# FLEXQCM_V1_1.net
KiCad netlist of a schematic drawn in EAGLE
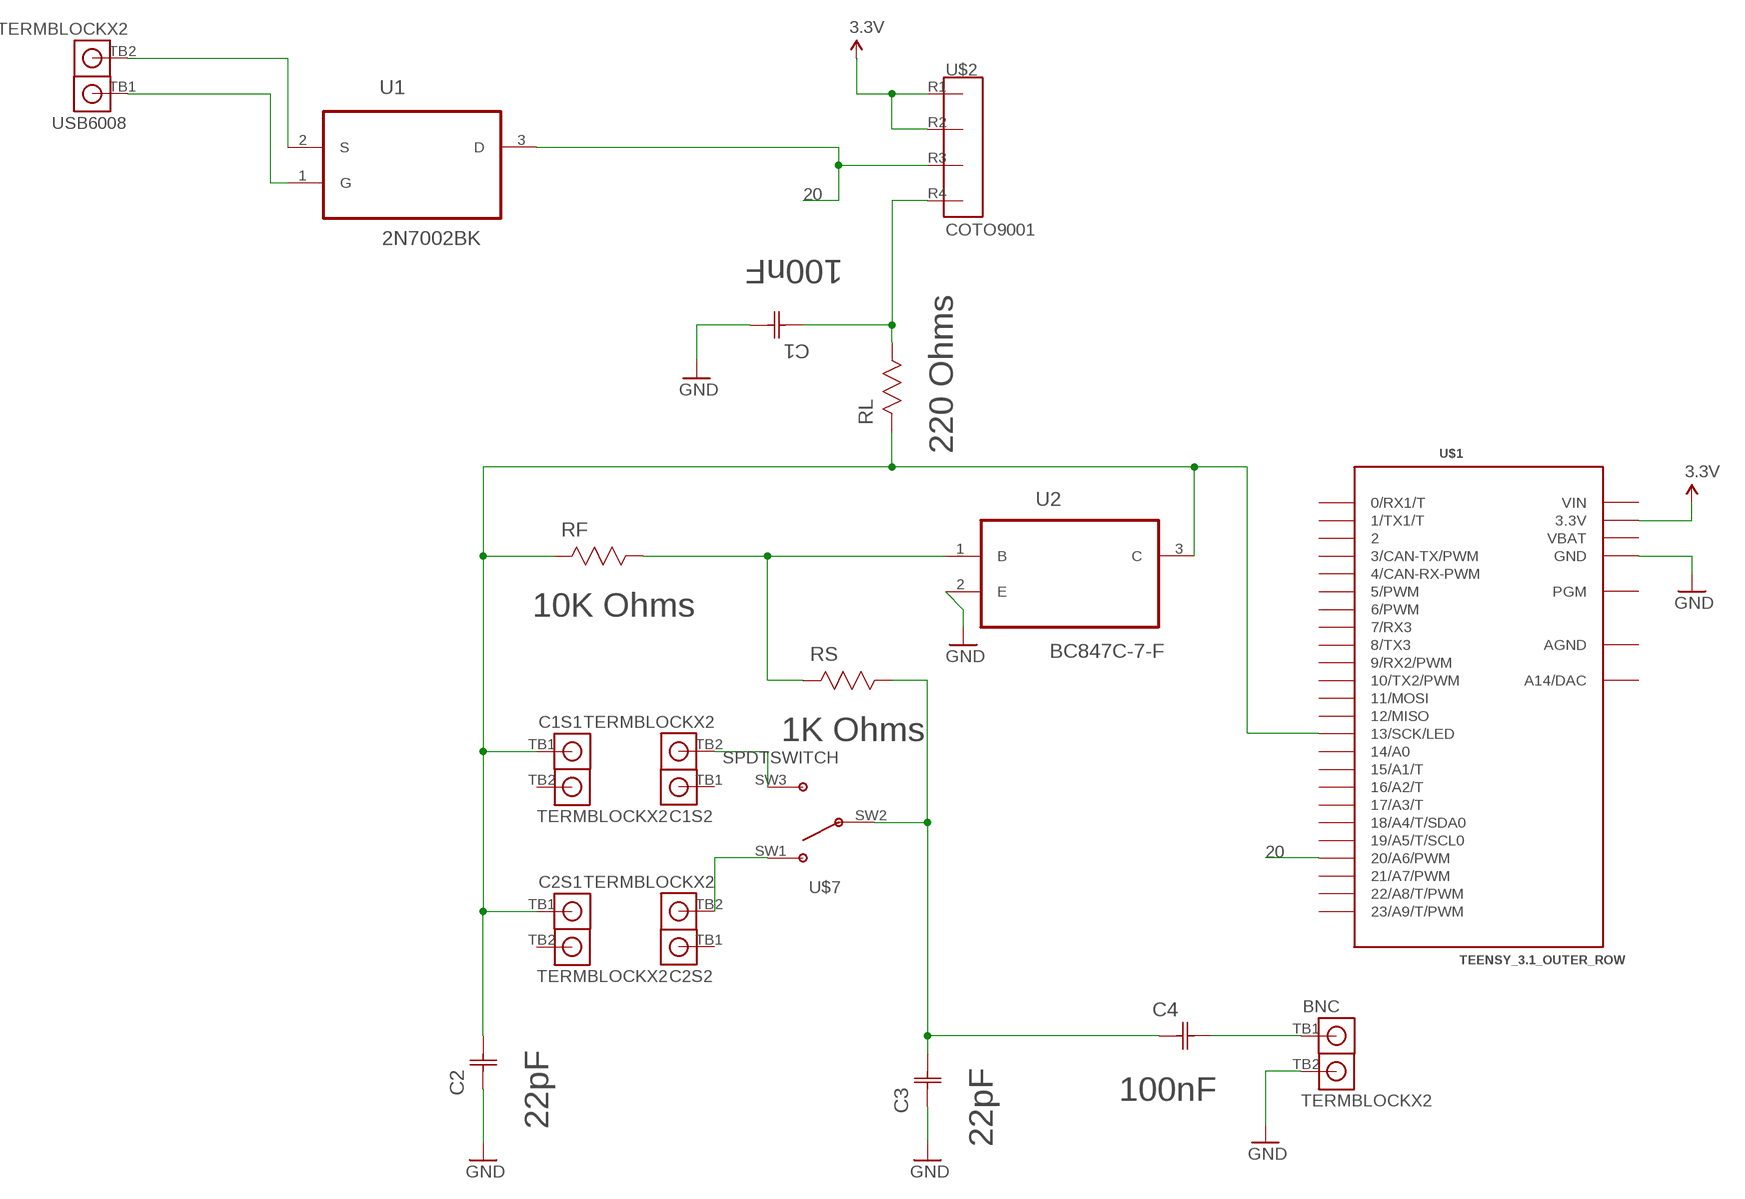
[diagram p0: schematic, sheet 1]

(export (version "E")
  (design (tool "Eeschema 10.0.6"))
  (components
    (comp (ref "BNC")
      (value "TERMBLOCKX2")
      (footprint "eagle-import:TERMBLOCKX2")
      (libsource (lib "eagle-import") (part "TERMBLOCKX2"))
    )
    (comp (ref "C1")
      (value "100nF")
      (footprint "eagle-import:CAPC3216X88N")
      (fields (field (name "MPN") "C1206C104K1RACTU") (field (name "TOLERANCE") "±10%"))
      (libsource (lib "eagle-import") (part "C1206C104K1RACTU"))
    )
    (comp (ref "C1S1")
      (value "TERMBLOCKX2")
      (footprint "eagle-import:TERMBLOCKX2")
      (libsource (lib "eagle-import") (part "TERMBLOCKX2"))
    )
    (comp (ref "C1S2")
      (value "TERMBLOCKX2")
      (footprint "eagle-import:TERMBLOCKX2")
      (libsource (lib "eagle-import") (part "TERMBLOCKX2"))
    )
    (comp (ref "C2")
      (value "22pF")
      (footprint "eagle-import:CAPC3216X88N")
      (fields (field (name "MPN") "C1206C220J5GACTU") (field (name "TOLERANCE") "±5%"))
      (libsource (lib "eagle-import") (part "C1206C220J5GACTU"))
    )
    (comp (ref "C2S1")
      (value "TERMBLOCKX2")
      (footprint "eagle-import:TERMBLOCKX2")
      (libsource (lib "eagle-import") (part "TERMBLOCKX2"))
    )
    (comp (ref "C2S2")
      (value "TERMBLOCKX2")
      (footprint "eagle-import:TERMBLOCKX2")
      (libsource (lib "eagle-import") (part "TERMBLOCKX2"))
    )
    (comp (ref "C3")
      (value "22pF")
      (footprint "eagle-import:CAPC3216X88N")
      (fields (field (name "MPN") "C1206C220J5GACTU") (field (name "TOLERANCE") "±5%"))
      (libsource (lib "eagle-import") (part "C1206C220J5GACTU"))
    )
    (comp (ref "C4")
      (value "100nF")
      (footprint "eagle-import:CAPC3216X88N")
      (fields (field (name "MPN") "C1206C104K1RACTU") (field (name "TOLERANCE") "±10%"))
      (libsource (lib "eagle-import") (part "C1206C104K1RACTU"))
    )
    (comp (ref "RF")
      (value "10K Ohms")
      (footprint "eagle-import:RESC3216X71N")
      (fields (field (name "MPN") "CRCW120610K0FKEA") (field (name "TOLERANCE") "±1%"))
      (libsource (lib "eagle-import") (part "CRCW120610K0FKEA"))
    )
    (comp (ref "RL")
      (value "220 Ohms")
      (footprint "eagle-import:RESC3216X71N")
      (fields (field (name "MPN") "CRCW1206220RJNEA") (field (name "TOLERANCE") "±5%"))
      (libsource (lib "eagle-import") (part "CRCW1206220RJNEA"))
    )
    (comp (ref "RS")
      (value "1K Ohms")
      (footprint "eagle-import:RESC3216X71N")
      (fields (field (name "MPN") "CRCW12061K00FKEA") (field (name "TOLERANCE") "±1%"))
      (libsource (lib "eagle-import") (part "CRCW12061K00FKEA"))
    )
    (comp (ref "U$1")
      (value "TEENSY_3.1_OUTER_ROW")
      (footprint "eagle-import:TEENSY3-OUTER_ROW")
      (libsource (lib "eagle-import") (part "TEENSY_3.1_OUTER_ROW"))
    )
    (comp (ref "U$2")
      (value "COTO9001")
      (footprint "eagle-import:COTO9001")
      (libsource (lib "eagle-import") (part "COTO9001"))
    )
    (comp (ref "U$7")
      (value "SPDTSWITCH")
      (footprint "eagle-import:SPDTSWITCH")
      (libsource (lib "eagle-import") (part "SPDTSWITCH"))
    )
    (comp (ref "U1")
      (value "2N7002BK")
      (footprint "eagle-import:SOT95P230X110-3N")
      (libsource (lib "eagle-import") (part "2N7002BK"))
    )
    (comp (ref "U2")
      (value "BC847C-7-F")
      (footprint "eagle-import:SOT103P240X110-3N")
      (libsource (lib "eagle-import") (part "BC847C-7-F"))
    )
    (comp (ref "USB6008")
      (value "TERMBLOCKX2")
      (footprint "eagle-import:TERMBLOCKX2")
      (libsource (lib "eagle-import") (part "TERMBLOCKX2"))
    )
  )
  (nets
    (net (code "1") (name "/20") (class "Default")
      (node (ref "U$1") (pin "20/A6") (pinfunction "20/A6/PWM_20/A6") (pintype "bidirectional"))
      (node (ref "U$2") (pin "R3") (pinfunction "R3_R3") (pintype "bidirectional"))
      (node (ref "U1") (pin "3") (pinfunction "D_3") (pintype "passive"))
    )
    (net (code "2") (name "/AGND") (class "Default")
      (node (ref "U$1") (pin "AGND") (pinfunction "AGND_AGND") (pintype "power_in"))
    )
    (net (code "3") (name "/VBAT") (class "Default")
      (node (ref "U$1") (pin "VBAT") (pinfunction "VBAT_VBAT") (pintype "power_in"))
    )
    (net (code "4") (name "/VIN") (class "Default")
      (node (ref "U$1") (pin "VIN") (pinfunction "VIN_VIN") (pintype "power_in"))
    )
    (net (code "5") (name "3.3V") (class "Default")
      (node (ref "U$1") (pin "3.3V") (pinfunction "3.3V_3.3V") (pintype "power_in"))
      (node (ref "U$1") (pin "3.3V1") (pinfunction "3.3V_3.3V1") (pintype "power_in"))
      (node (ref "U$2") (pin "R1") (pinfunction "R1_R1") (pintype "bidirectional"))
      (node (ref "U$2") (pin "R2") (pinfunction "R2_R2") (pintype "bidirectional"))
    )
    (net (code "6") (name "GND") (class "Default")
      (node (ref "BNC") (pin "TB2") (pinfunction "TB2_TB2") (pintype "bidirectional"))
      (node (ref "C1") (pin "2") (pinfunction "C2_2") (pintype "passive"))
      (node (ref "C2") (pin "1") (pinfunction "C1_1") (pintype "passive"))
      (node (ref "C3") (pin "1") (pinfunction "C1_1") (pintype "passive"))
      (node (ref "U$1") (pin "GND") (pinfunction "GND_GND") (pintype "power_in"))
      (node (ref "U$1") (pin "GND1") (pinfunction "GND_GND1") (pintype "power_in"))
      (node (ref "U2") (pin "2") (pinfunction "E_2") (pintype "passive"))
    )
    (net (code "7") (name "Net-(C1-C1)") (class "Default")
      (node (ref "C1") (pin "1") (pinfunction "C1_1") (pintype "passive"))
      (node (ref "RL") (pin "1") (pinfunction "1_1") (pintype "passive"))
      (node (ref "U$2") (pin "R4") (pinfunction "R4_R4") (pintype "bidirectional"))
    )
    (net (code "8") (name "Net-(C1S2-PadTB2)") (class "Default")
      (node (ref "C1S2") (pin "TB2") (pinfunction "TB2_TB2") (pintype "bidirectional"))
      (node (ref "U$7") (pin "SW3") (pinfunction "SW3_SW3") (pintype "bidirectional"))
    )
    (net (code "9") (name "Net-(C2-C2)") (class "Default")
      (node (ref "C1S1") (pin "TB1") (pinfunction "TB1_TB1") (pintype "bidirectional"))
      (node (ref "C2") (pin "2") (pinfunction "C2_2") (pintype "passive"))
      (node (ref "C2S1") (pin "TB1") (pinfunction "TB1_TB1") (pintype "bidirectional"))
      (node (ref "RF") (pin "2") (pinfunction "2_2") (pintype "passive"))
      (node (ref "RL") (pin "2") (pinfunction "2_2") (pintype "passive"))
      (node (ref "U$1") (pin "13") (pinfunction "13/SCK/LED_13") (pintype "bidirectional"))
      (node (ref "U2") (pin "3") (pinfunction "C_3") (pintype "output"))
    )
    (net (code "10") (name "Net-(C2S2-PadTB2)") (class "Default")
      (node (ref "C2S2") (pin "TB2") (pinfunction "TB2_TB2") (pintype "bidirectional"))
      (node (ref "U$7") (pin "SW1") (pinfunction "SW1_SW1") (pintype "bidirectional"))
    )
    (net (code "11") (name "Net-(C3-C2)") (class "Default")
      (node (ref "C3") (pin "2") (pinfunction "C2_2") (pintype "passive"))
      (node (ref "C4") (pin "1") (pinfunction "C1_1") (pintype "passive"))
      (node (ref "RS") (pin "1") (pinfunction "1_1") (pintype "passive"))
      (node (ref "U$7") (pin "SW2") (pinfunction "SW2_SW2") (pintype "bidirectional"))
    )
    (net (code "12") (name "Net-(C4-C2)") (class "Default")
      (node (ref "BNC") (pin "TB1") (pinfunction "TB1_TB1") (pintype "bidirectional"))
      (node (ref "C4") (pin "2") (pinfunction "C2_2") (pintype "passive"))
    )
    (net (code "13") (name "Net-(U1-G)") (class "Default")
      (node (ref "U1") (pin "1") (pinfunction "G_1") (pintype "passive"))
      (node (ref "USB6008") (pin "TB1") (pinfunction "TB1_TB1") (pintype "bidirectional"))
    )
    (net (code "14") (name "Net-(U1-S)") (class "Default")
      (node (ref "U1") (pin "2") (pinfunction "S_2") (pintype "passive"))
      (node (ref "USB6008") (pin "TB2") (pinfunction "TB2_TB2") (pintype "bidirectional"))
    )
    (net (code "15") (name "Net-(U2-B)") (class "Default")
      (node (ref "RF") (pin "1") (pinfunction "1_1") (pintype "passive"))
      (node (ref "RS") (pin "2") (pinfunction "2_2") (pintype "passive"))
      (node (ref "U2") (pin "1") (pinfunction "B_1") (pintype "input"))
    )
    (net (code "16") (name "unconnected-(C1S1-PadTB2)") (class "Default")
      (node (ref "C1S1") (pin "TB2") (pinfunction "TB2_TB2") (pintype "bidirectional"))
    )
    (net (code "17") (name "unconnected-(C1S2-PadTB1)") (class "Default")
      (node (ref "C1S2") (pin "TB1") (pinfunction "TB1_TB1") (pintype "bidirectional"))
    )
    (net (code "18") (name "unconnected-(C2S1-PadTB2)") (class "Default")
      (node (ref "C2S1") (pin "TB2") (pinfunction "TB2_TB2") (pintype "bidirectional"))
    )
    (net (code "19") (name "unconnected-(C2S2-PadTB1)") (class "Default")
      (node (ref "C2S2") (pin "TB1") (pinfunction "TB1_TB1") (pintype "bidirectional"))
    )
    (net (code "20") (name "unconnected-(U$1-0{slash}RX1{slash}T-Pad0)") (class "Default")
      (node (ref "U$1") (pin "0") (pinfunction "0/RX1/T_0") (pintype "bidirectional"))
    )
    (net (code "21") (name "unconnected-(U$1-1{slash}TX1{slash}T-Pad1)") (class "Default")
      (node (ref "U$1") (pin "1") (pinfunction "1/TX1/T_1") (pintype "bidirectional"))
    )
    (net (code "22") (name "unconnected-(U$1-3{slash}CAN-TX{slash}PWM-Pad3)") (class "Default")
      (node (ref "U$1") (pin "3") (pinfunction "3/CAN-TX/PWM_3") (pintype "bidirectional"))
    )
    (net (code "23") (name "unconnected-(U$1-4{slash}CAN-RX-PWM-Pad4)") (class "Default")
      (node (ref "U$1") (pin "4") (pinfunction "4/CAN-RX-PWM_4") (pintype "bidirectional"))
    )
    (net (code "24") (name "unconnected-(U$1-5{slash}PWM-Pad5)") (class "Default")
      (node (ref "U$1") (pin "5") (pinfunction "5/PWM_5") (pintype "bidirectional"))
    )
    (net (code "25") (name "unconnected-(U$1-6{slash}PWM-Pad6)") (class "Default")
      (node (ref "U$1") (pin "6") (pinfunction "6/PWM_6") (pintype "bidirectional"))
    )
    (net (code "26") (name "unconnected-(U$1-7{slash}RX3-Pad7)") (class "Default")
      (node (ref "U$1") (pin "7") (pinfunction "7/RX3_7") (pintype "bidirectional"))
    )
    (net (code "27") (name "unconnected-(U$1-8{slash}TX3-Pad8)") (class "Default")
      (node (ref "U$1") (pin "8") (pinfunction "8/TX3_8") (pintype "bidirectional"))
    )
    (net (code "28") (name "unconnected-(U$1-9{slash}RX2{slash}PWM-Pad9)") (class "Default")
      (node (ref "U$1") (pin "9") (pinfunction "9/RX2/PWM_9") (pintype "bidirectional"))
    )
    (net (code "29") (name "unconnected-(U$1-10{slash}TX2{slash}PWM-Pad10)") (class "Default")
      (node (ref "U$1") (pin "10") (pinfunction "10/TX2/PWM_10") (pintype "bidirectional"))
    )
    (net (code "30") (name "unconnected-(U$1-11{slash}MOSI-Pad11)") (class "Default")
      (node (ref "U$1") (pin "11") (pinfunction "11/MOSI_11") (pintype "bidirectional"))
    )
    (net (code "31") (name "unconnected-(U$1-12{slash}MISO-Pad12)") (class "Default")
      (node (ref "U$1") (pin "12") (pinfunction "12/MISO_12") (pintype "bidirectional"))
    )
    (net (code "32") (name "unconnected-(U$1-15{slash}A1{slash}T-Pad15{slash}A1)") (class "Default")
      (node (ref "U$1") (pin "15/A1") (pinfunction "15/A1/T_15/A1") (pintype "bidirectional"))
    )
    (net (code "33") (name "unconnected-(U$1-16{slash}A2{slash}T-Pad16{slash}A2)") (class "Default")
      (node (ref "U$1") (pin "16/A2") (pinfunction "16/A2/T_16/A2") (pintype "bidirectional"))
    )
    (net (code "34") (name "unconnected-(U$1-17{slash}A3{slash}T-Pad17{slash}A3)") (class "Default")
      (node (ref "U$1") (pin "17/A3") (pinfunction "17/A3/T_17/A3") (pintype "bidirectional"))
    )
    (net (code "35") (name "unconnected-(U$1-18{slash}A4{slash}T{slash}SDA0-Pad18{slash}A4)") (class "Default")
      (node (ref "U$1") (pin "18/A4") (pinfunction "18/A4/T/SDA0_18/A4") (pintype "bidirectional"))
    )
    (net (code "36") (name "unconnected-(U$1-19{slash}A5{slash}T{slash}SCL0-Pad19{slash}A5)") (class "Default")
      (node (ref "U$1") (pin "19/A5") (pinfunction "19/A5/T/SCL0_19/A5") (pintype "bidirectional"))
    )
    (net (code "37") (name "unconnected-(U$1-21{slash}A7{slash}PWM-Pad21{slash}A7)") (class "Default")
      (node (ref "U$1") (pin "21/A7") (pinfunction "21/A7/PWM_21/A7") (pintype "bidirectional"))
    )
    (net (code "38") (name "unconnected-(U$1-22{slash}A8{slash}T{slash}PWM-Pad22{slash}A8)") (class "Default")
      (node (ref "U$1") (pin "22/A8") (pinfunction "22/A8/T/PWM_22/A8") (pintype "bidirectional"))
    )
    (net (code "39") (name "unconnected-(U$1-23{slash}A9{slash}T{slash}PWM-Pad23{slash}A9)") (class "Default")
      (node (ref "U$1") (pin "23/A9") (pinfunction "23/A9/T/PWM_23/A9") (pintype "bidirectional"))
    )
    (net (code "40") (name "unconnected-(U$1-A14{slash}DAC-PadRESET{slash}DAC)") (class "Default")
      (node (ref "U$1") (pin "RESET/DAC") (pinfunction "A14/DAC_RESET/DAC") (pintype "bidirectional"))
    )
    (net (code "41") (name "unconnected-(U$1-Pad2)") (class "Default")
      (node (ref "U$1") (pin "2") (pinfunction "2_2") (pintype "bidirectional"))
    )
    (net (code "42") (name "unconnected-(U$1-Pad14{slash}A0)") (class "Default")
      (node (ref "U$1") (pin "14/A0") (pinfunction "14/A0_14/A0") (pintype "bidirectional"))
    )
    (net (code "43") (name "unconnected-(U$1-PadPGM)") (class "Default")
      (node (ref "U$1") (pin "PGM") (pinfunction "PGM_PGM") (pintype "bidirectional"))
    )
  )
)
